# M105.net
KiCad netlist of a schematic drawn in EAGLE
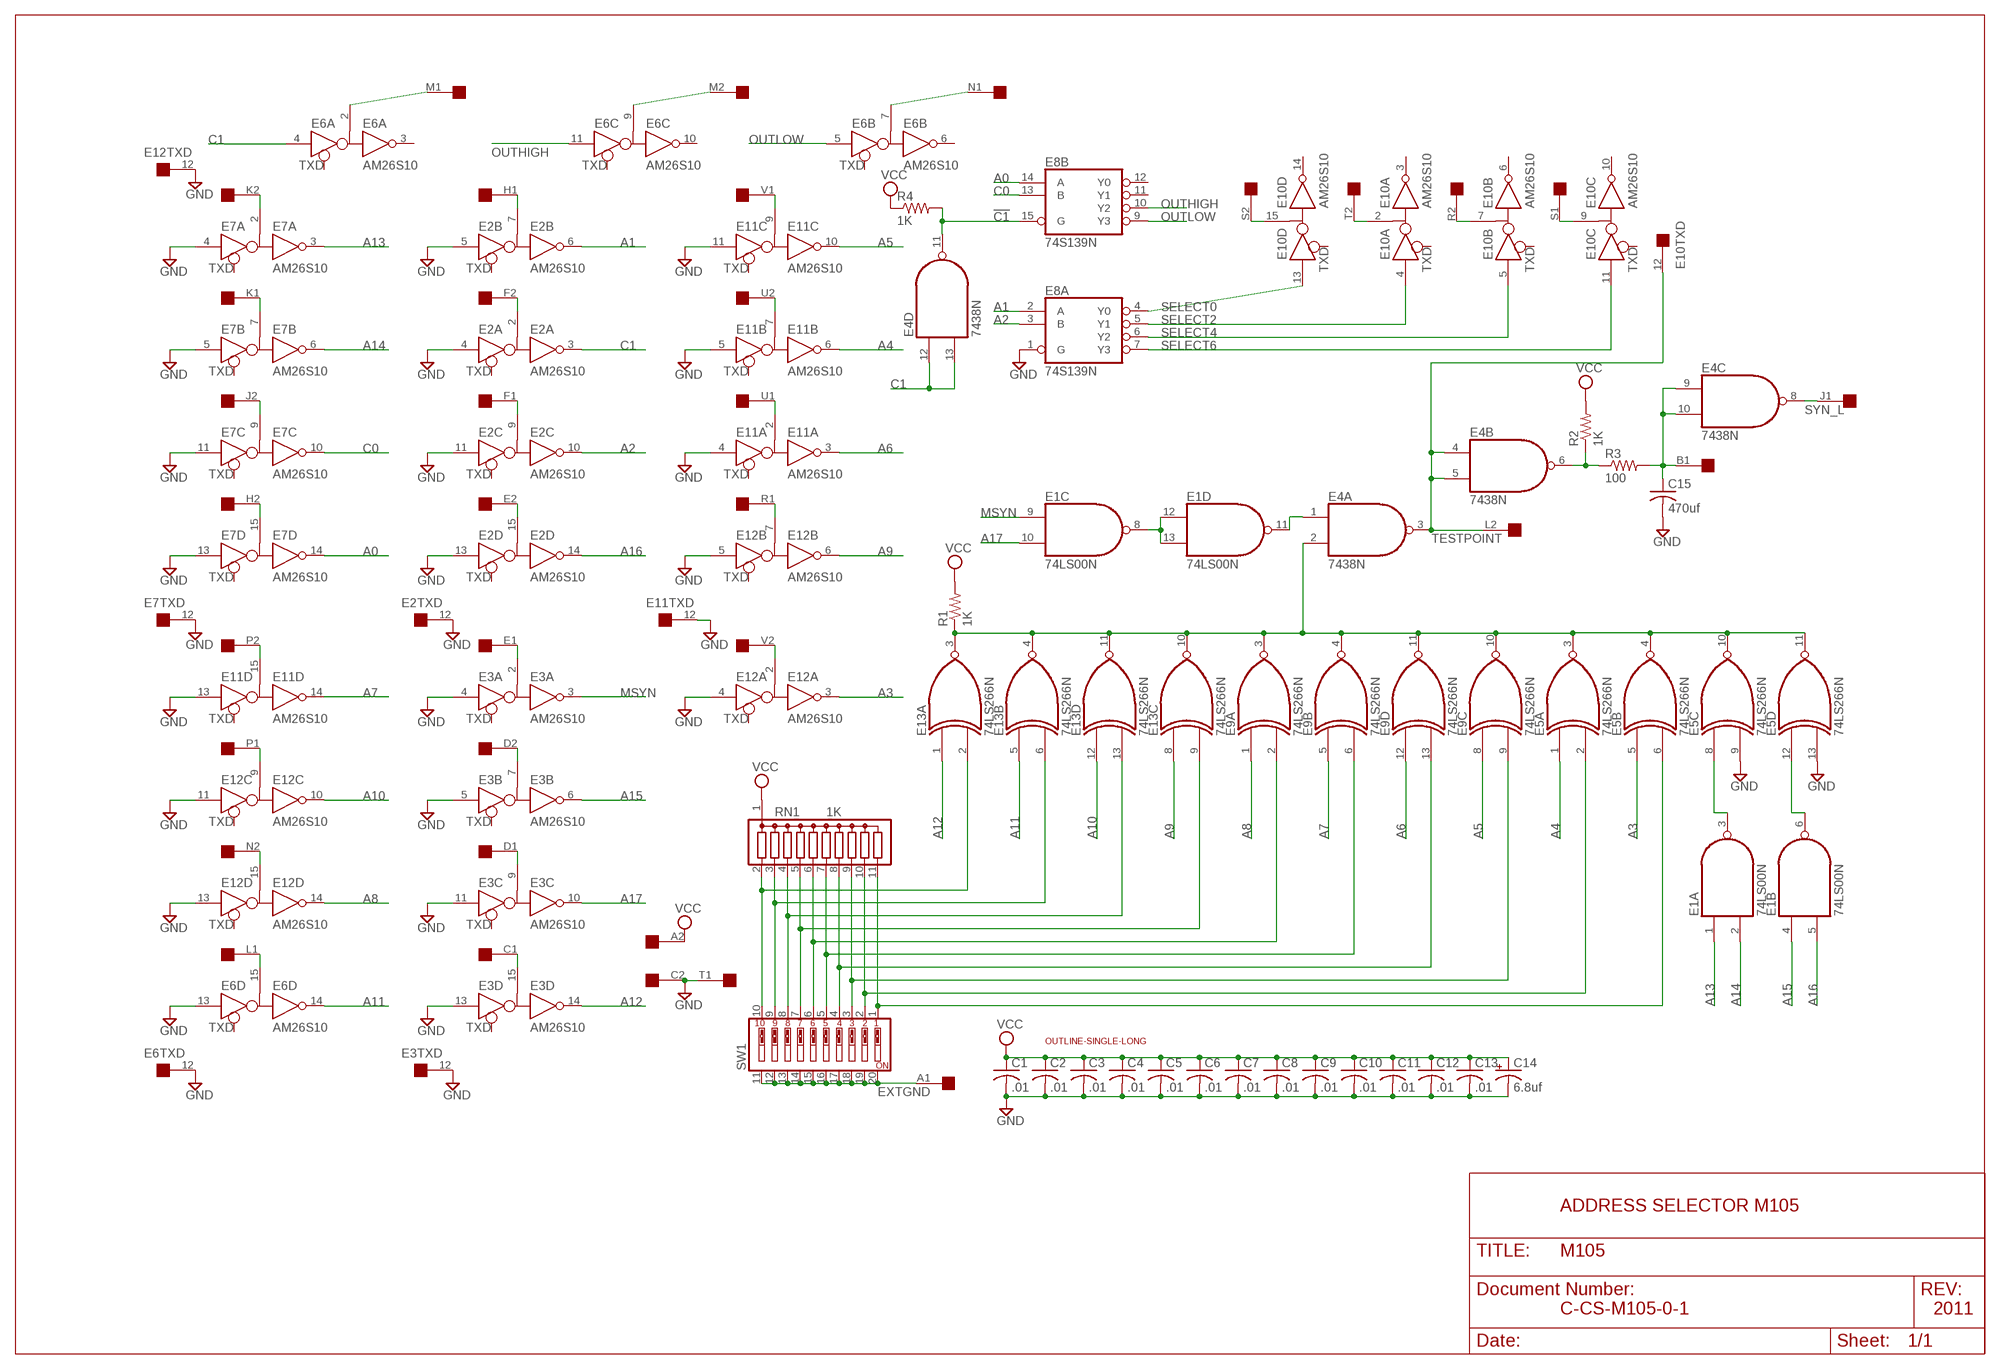
[diagram p0: schematic, sheet 1]

(export (version "E")
  (design (tool "Eeschema 10.0.6"))
  (components
    (comp (ref "C1")
      (value ".01")
      (footprint "eagle-import:C050-025X075")
      (libsource (lib "eagle-import") (part "C-US050-025X075"))
    )
    (comp (ref "C2")
      (value ".01")
      (footprint "eagle-import:C050-025X075")
      (libsource (lib "eagle-import") (part "C-US050-025X075"))
    )
    (comp (ref "C3")
      (value ".01")
      (footprint "eagle-import:C050-025X075")
      (libsource (lib "eagle-import") (part "C-US050-025X075"))
    )
    (comp (ref "C4")
      (value ".01")
      (footprint "eagle-import:C050-025X075")
      (libsource (lib "eagle-import") (part "C-US050-025X075"))
    )
    (comp (ref "C5")
      (value ".01")
      (footprint "eagle-import:C050-025X075")
      (libsource (lib "eagle-import") (part "C-US050-025X075"))
    )
    (comp (ref "C6")
      (value ".01")
      (footprint "eagle-import:C050-025X075")
      (libsource (lib "eagle-import") (part "C-US050-025X075"))
    )
    (comp (ref "C7")
      (value ".01")
      (footprint "eagle-import:C050-025X075")
      (libsource (lib "eagle-import") (part "C-US050-025X075"))
    )
    (comp (ref "C8")
      (value ".01")
      (footprint "eagle-import:C050-025X075")
      (libsource (lib "eagle-import") (part "C-US050-025X075"))
    )
    (comp (ref "C9")
      (value ".01")
      (footprint "eagle-import:C050-025X075")
      (libsource (lib "eagle-import") (part "C-US050-025X075"))
    )
    (comp (ref "C10")
      (value ".01")
      (footprint "eagle-import:C050-025X075")
      (libsource (lib "eagle-import") (part "C-US050-025X075"))
    )
    (comp (ref "C11")
      (value ".01")
      (footprint "eagle-import:C050-025X075")
      (libsource (lib "eagle-import") (part "C-US050-025X075"))
    )
    (comp (ref "C12")
      (value ".01")
      (footprint "eagle-import:C050-025X075")
      (libsource (lib "eagle-import") (part "C-US050-025X075"))
    )
    (comp (ref "C13")
      (value ".01")
      (footprint "eagle-import:C050-025X075")
      (libsource (lib "eagle-import") (part "C-US050-025X075"))
    )
    (comp (ref "C14")
      (value "6.8uf")
      (footprint "eagle-import:E15-5")
      (libsource (lib "eagle-import") (part "CPOL-USE15-5AXIAL"))
    )
    (comp (ref "C15")
      (value "470uf")
      (footprint "eagle-import:C050-025X075")
      (libsource (lib "eagle-import") (part "C-US050-025X075"))
    )
    (comp (ref "E1")
      (value "74LS00N")
      (footprint "eagle-import:DIL14")
      (libsource (lib "eagle-import") (part "7400NLS"))
    )
    (comp (ref "E2")
      (value "AM26S10")
      (footprint "eagle-import:DIL16")
      (libsource (lib "eagle-import") (part "AM26S10"))
    )
    (comp (ref "E3")
      (value "AM26S10")
      (footprint "eagle-import:DIL16")
      (libsource (lib "eagle-import") (part "AM26S10"))
    )
    (comp (ref "E4")
      (value "7438N")
      (footprint "eagle-import:DIL14")
      (libsource (lib "eagle-import") (part "7438N"))
    )
    (comp (ref "E5")
      (value "74LS266N")
      (footprint "eagle-import:DIL14")
      (libsource (lib "eagle-import") (part "74266NLS"))
    )
    (comp (ref "E6")
      (value "AM26S10")
      (footprint "eagle-import:DIL16")
      (libsource (lib "eagle-import") (part "AM26S10"))
    )
    (comp (ref "E7")
      (value "AM26S10")
      (footprint "eagle-import:DIL16")
      (libsource (lib "eagle-import") (part "AM26S10"))
    )
    (comp (ref "E8")
      (value "74S139N")
      (footprint "eagle-import:DIL16")
      (libsource (lib "eagle-import") (part "74139NS"))
    )
    (comp (ref "E9")
      (value "74LS266N")
      (footprint "eagle-import:DIL14")
      (libsource (lib "eagle-import") (part "74266NLS"))
    )
    (comp (ref "E10")
      (value "AM26S10")
      (footprint "eagle-import:DIL16")
      (libsource (lib "eagle-import") (part "AM26S10"))
    )
    (comp (ref "E11")
      (value "AM26S10")
      (footprint "eagle-import:DIL16")
      (libsource (lib "eagle-import") (part "AM26S10"))
    )
    (comp (ref "E12")
      (value "AM26S10")
      (footprint "eagle-import:DIL16")
      (libsource (lib "eagle-import") (part "AM26S10"))
    )
    (comp (ref "E13")
      (value "74LS266N")
      (footprint "eagle-import:DIL14")
      (libsource (lib "eagle-import") (part "74266NLS"))
    )
    (comp (ref "R1")
      (value "1K")
      (footprint "eagle-import:0207_10")
      (libsource (lib "eagle-import") (part "R-US_0207/10"))
    )
    (comp (ref "R2")
      (value "1K")
      (footprint "eagle-import:0207_10")
      (libsource (lib "eagle-import") (part "R-US_0207/10"))
    )
    (comp (ref "R3")
      (value "100")
      (footprint "eagle-import:0207_10")
      (libsource (lib "eagle-import") (part "R-US_0207/10"))
    )
    (comp (ref "R4")
      (value "1K")
      (footprint "eagle-import:0207_10")
      (libsource (lib "eagle-import") (part "R-US_0207/10"))
    )
    (comp (ref "RN1")
      (value "1K")
      (footprint "eagle-import:SIL11")
      (libsource (lib "eagle-import") (part "G10R"))
    )
    (comp (ref "SW1")
      (value "SW_DIP-10")
      (footprint "eagle-import:EDG-10")
      (libsource (lib "eagle-import") (part "SW_DIP-10"))
    )
    (comp (ref "U$1")
      (value "SINGLE")
      (footprint "eagle-import:EDGE-CON2")
      (libsource (lib "eagle-import") (part "SINGLE"))
    )
    (comp (ref "U$2")
      (value "OUTLINE-SINGLE-LONG")
      (footprint "eagle-import:SINGLE-LONG")
      (libsource (lib "eagle-import") (part "OUTLINE-SINGLE-LONG"))
    )
  )
  (nets
    (net (code "1") (name "/A0") (class "Default")
      (node (ref "E7") (pin "14") (pinfunction "R_14") (pintype "output"))
      (node (ref "E8") (pin "14") (pinfunction "A_14") (pintype "input"))
    )
    (net (code "2") (name "/A1") (class "Default")
      (node (ref "E2") (pin "6") (pinfunction "R_6") (pintype "output"))
      (node (ref "E8") (pin "2") (pinfunction "A_2") (pintype "input"))
    )
    (net (code "3") (name "/A2") (class "Default")
      (node (ref "E2") (pin "10") (pinfunction "R_10") (pintype "output"))
      (node (ref "E8") (pin "3") (pinfunction "B_3") (pintype "input"))
    )
    (net (code "4") (name "/A3") (class "Default")
      (node (ref "E12") (pin "3") (pinfunction "R_3") (pintype "output"))
      (node (ref "E5") (pin "5") (pinfunction "I0_5") (pintype "input"))
    )
    (net (code "5") (name "/A4") (class "Default")
      (node (ref "E11") (pin "6") (pinfunction "R_6") (pintype "output"))
      (node (ref "E5") (pin "1") (pinfunction "I0_1") (pintype "input"))
    )
    (net (code "6") (name "/A5") (class "Default")
      (node (ref "E11") (pin "10") (pinfunction "R_10") (pintype "output"))
      (node (ref "E9") (pin "8") (pinfunction "I0_8") (pintype "input"))
    )
    (net (code "7") (name "/A6") (class "Default")
      (node (ref "E11") (pin "3") (pinfunction "R_3") (pintype "output"))
      (node (ref "E9") (pin "12") (pinfunction "I0_12") (pintype "input"))
    )
    (net (code "8") (name "/A7") (class "Default")
      (node (ref "E11") (pin "14") (pinfunction "R_14") (pintype "output"))
      (node (ref "E9") (pin "5") (pinfunction "I0_5") (pintype "input"))
    )
    (net (code "9") (name "/A8") (class "Default")
      (node (ref "E12") (pin "14") (pinfunction "R_14") (pintype "output"))
      (node (ref "E9") (pin "1") (pinfunction "I0_1") (pintype "input"))
    )
    (net (code "10") (name "/A9") (class "Default")
      (node (ref "E12") (pin "6") (pinfunction "R_6") (pintype "output"))
      (node (ref "E13") (pin "8") (pinfunction "I0_8") (pintype "input"))
    )
    (net (code "11") (name "/A10") (class "Default")
      (node (ref "E12") (pin "10") (pinfunction "R_10") (pintype "output"))
      (node (ref "E13") (pin "12") (pinfunction "I0_12") (pintype "input"))
    )
    (net (code "12") (name "/A11") (class "Default")
      (node (ref "E13") (pin "5") (pinfunction "I0_5") (pintype "input"))
      (node (ref "E6") (pin "14") (pinfunction "R_14") (pintype "output"))
    )
    (net (code "13") (name "/A12") (class "Default")
      (node (ref "E13") (pin "1") (pinfunction "I0_1") (pintype "input"))
      (node (ref "E3") (pin "14") (pinfunction "R_14") (pintype "output"))
    )
    (net (code "14") (name "/A13") (class "Default")
      (node (ref "E1") (pin "1") (pinfunction "I0_1") (pintype "input"))
      (node (ref "E7") (pin "3") (pinfunction "R_3") (pintype "output"))
    )
    (net (code "15") (name "/A14") (class "Default")
      (node (ref "E1") (pin "2") (pinfunction "I1_2") (pintype "input"))
      (node (ref "E7") (pin "6") (pinfunction "R_6") (pintype "output"))
    )
    (net (code "16") (name "/A15") (class "Default")
      (node (ref "E1") (pin "4") (pinfunction "I0_4") (pintype "input"))
      (node (ref "E3") (pin "6") (pinfunction "R_6") (pintype "output"))
    )
    (net (code "17") (name "/A16") (class "Default")
      (node (ref "E1") (pin "5") (pinfunction "I1_5") (pintype "input"))
      (node (ref "E2") (pin "14") (pinfunction "R_14") (pintype "output"))
    )
    (net (code "18") (name "/A17") (class "Default")
      (node (ref "E1") (pin "10") (pinfunction "I1_10") (pintype "input"))
      (node (ref "E3") (pin "10") (pinfunction "R_10") (pintype "output"))
    )
    (net (code "19") (name "/C0") (class "Default")
      (node (ref "E7") (pin "10") (pinfunction "R_10") (pintype "output"))
      (node (ref "E8") (pin "13") (pinfunction "B_13") (pintype "input"))
    )
    (net (code "20") (name "/C1") (class "Default")
      (node (ref "E2") (pin "3") (pinfunction "R_3") (pintype "output"))
      (node (ref "E4") (pin "12") (pinfunction "I0_12") (pintype "input"))
      (node (ref "E4") (pin "13") (pinfunction "I1_13") (pintype "input"))
      (node (ref "E6") (pin "4") (pinfunction "D_4") (pintype "input"))
    )
    (net (code "21") (name "/EXTGND") (class "Default")
      (node (ref "SW1") (pin "11") (pinfunction "11_11") (pintype "passive"))
      (node (ref "SW1") (pin "12") (pinfunction "12_12") (pintype "passive"))
      (node (ref "SW1") (pin "13") (pinfunction "13_13") (pintype "passive"))
      (node (ref "SW1") (pin "14") (pinfunction "14_14") (pintype "passive"))
      (node (ref "SW1") (pin "15") (pinfunction "15_15") (pintype "passive"))
      (node (ref "SW1") (pin "16") (pinfunction "16_16") (pintype "passive"))
      (node (ref "SW1") (pin "17") (pinfunction "17_17") (pintype "passive"))
      (node (ref "SW1") (pin "18") (pinfunction "18_18") (pintype "passive"))
      (node (ref "SW1") (pin "19") (pinfunction "19_19") (pintype "passive"))
      (node (ref "SW1") (pin "20") (pinfunction "20_20") (pintype "passive"))
      (node (ref "U$1") (pin "A1") (pinfunction "1_A1") (pintype "bidirectional"))
    )
    (net (code "22") (name "/MSYN") (class "Default")
      (node (ref "E1") (pin "9") (pinfunction "I0_9") (pintype "input"))
      (node (ref "E3") (pin "3") (pinfunction "R_3") (pintype "output"))
    )
    (net (code "23") (name "/OUTHIGH") (class "Default")
      (node (ref "E6") (pin "11") (pinfunction "D_11") (pintype "input"))
      (node (ref "E8") (pin "10") (pinfunction "Y2_10") (pintype "output"))
    )
    (net (code "24") (name "/OUTLOW") (class "Default")
      (node (ref "E6") (pin "5") (pinfunction "D_5") (pintype "input"))
      (node (ref "E8") (pin "9") (pinfunction "Y3_9") (pintype "output"))
    )
    (net (code "25") (name "/SELECT0") (class "Default")
      (node (ref "E10") (pin "13") (pinfunction "D_13") (pintype "input"))
      (node (ref "E8") (pin "4") (pinfunction "Y0_4") (pintype "output"))
    )
    (net (code "26") (name "/SELECT2") (class "Default")
      (node (ref "E10") (pin "4") (pinfunction "D_4") (pintype "input"))
      (node (ref "E8") (pin "5") (pinfunction "Y1_5") (pintype "output"))
    )
    (net (code "27") (name "/SELECT4") (class "Default")
      (node (ref "E10") (pin "5") (pinfunction "D_5") (pintype "input"))
      (node (ref "E8") (pin "6") (pinfunction "Y2_6") (pintype "output"))
    )
    (net (code "28") (name "/SELECT6") (class "Default")
      (node (ref "E10") (pin "11") (pinfunction "D_11") (pintype "input"))
      (node (ref "E8") (pin "7") (pinfunction "Y3_7") (pintype "output"))
    )
    (net (code "29") (name "/SYN_L") (class "Default")
      (node (ref "E4") (pin "8") (pinfunction "O_8") (pintype "open_collector"))
      (node (ref "U$1") (pin "J1") (pinfunction "1_J1") (pintype "bidirectional"))
    )
    (net (code "30") (name "/TESTPOINT") (class "Default")
      (node (ref "E10") (pin "12") (pinfunction "TXD_12") (pintype "input"))
      (node (ref "E4") (pin "3") (pinfunction "O_3") (pintype "open_collector"))
      (node (ref "E4") (pin "4") (pinfunction "I0_4") (pintype "input"))
      (node (ref "E4") (pin "5") (pinfunction "I1_5") (pintype "input"))
      (node (ref "U$1") (pin "L2") (pinfunction "1_L2") (pintype "bidirectional"))
    )
    (net (code "31") (name "/~{C1}") (class "Default")
      (node (ref "E4") (pin "11") (pinfunction "O_11") (pintype "open_collector"))
      (node (ref "E8") (pin "15") (pinfunction "G_15") (pintype "input"))
      (node (ref "R4") (pin "2") (pinfunction "2_2") (pintype "passive"))
    )
    (net (code "32") (name "GND") (class "Default")
      (node (ref "C1") (pin "2") (pinfunction "2_2") (pintype "passive"))
      (node (ref "C10") (pin "2") (pinfunction "2_2") (pintype "passive"))
      (node (ref "C11") (pin "2") (pinfunction "2_2") (pintype "passive"))
      (node (ref "C12") (pin "2") (pinfunction "2_2") (pintype "passive"))
      (node (ref "C13") (pin "2") (pinfunction "2_2") (pintype "passive"))
      (node (ref "C14") (pin "-") (pinfunction "-_-") (pintype "passive"))
      (node (ref "C15") (pin "2") (pinfunction "2_2") (pintype "passive"))
      (node (ref "C2") (pin "2") (pinfunction "2_2") (pintype "passive"))
      (node (ref "C3") (pin "2") (pinfunction "2_2") (pintype "passive"))
      (node (ref "C4") (pin "2") (pinfunction "2_2") (pintype "passive"))
      (node (ref "C5") (pin "2") (pinfunction "2_2") (pintype "passive"))
      (node (ref "C6") (pin "2") (pinfunction "2_2") (pintype "passive"))
      (node (ref "C7") (pin "2") (pinfunction "2_2") (pintype "passive"))
      (node (ref "C8") (pin "2") (pinfunction "2_2") (pintype "passive"))
      (node (ref "C9") (pin "2") (pinfunction "2_2") (pintype "passive"))
      (node (ref "E11") (pin "11") (pinfunction "D_11") (pintype "input"))
      (node (ref "E11") (pin "12") (pinfunction "TXD_12") (pintype "input"))
      (node (ref "E11") (pin "13") (pinfunction "D_13") (pintype "input"))
      (node (ref "E11") (pin "4") (pinfunction "D_4") (pintype "input"))
      (node (ref "E11") (pin "5") (pinfunction "D_5") (pintype "input"))
      (node (ref "E12") (pin "11") (pinfunction "D_11") (pintype "input"))
      (node (ref "E12") (pin "12") (pinfunction "TXD_12") (pintype "input"))
      (node (ref "E12") (pin "13") (pinfunction "D_13") (pintype "input"))
      (node (ref "E12") (pin "4") (pinfunction "D_4") (pintype "input"))
      (node (ref "E12") (pin "5") (pinfunction "D_5") (pintype "input"))
      (node (ref "E2") (pin "11") (pinfunction "D_11") (pintype "input"))
      (node (ref "E2") (pin "12") (pinfunction "TXD_12") (pintype "input"))
      (node (ref "E2") (pin "13") (pinfunction "D_13") (pintype "input"))
      (node (ref "E2") (pin "4") (pinfunction "D_4") (pintype "input"))
      (node (ref "E2") (pin "5") (pinfunction "D_5") (pintype "input"))
      (node (ref "E3") (pin "11") (pinfunction "D_11") (pintype "input"))
      (node (ref "E3") (pin "12") (pinfunction "TXD_12") (pintype "input"))
      (node (ref "E3") (pin "13") (pinfunction "D_13") (pintype "input"))
      (node (ref "E3") (pin "4") (pinfunction "D_4") (pintype "input"))
      (node (ref "E3") (pin "5") (pinfunction "D_5") (pintype "input"))
      (node (ref "E5") (pin "13") (pinfunction "I1_13") (pintype "input"))
      (node (ref "E5") (pin "9") (pinfunction "I1_9") (pintype "input"))
      (node (ref "E6") (pin "12") (pinfunction "TXD_12") (pintype "input"))
      (node (ref "E6") (pin "13") (pinfunction "D_13") (pintype "input"))
      (node (ref "E7") (pin "11") (pinfunction "D_11") (pintype "input"))
      (node (ref "E7") (pin "12") (pinfunction "TXD_12") (pintype "input"))
      (node (ref "E7") (pin "13") (pinfunction "D_13") (pintype "input"))
      (node (ref "E7") (pin "4") (pinfunction "D_4") (pintype "input"))
      (node (ref "E7") (pin "5") (pinfunction "D_5") (pintype "input"))
      (node (ref "E8") (pin "1") (pinfunction "G_1") (pintype "input"))
      (node (ref "U$1") (pin "C2") (pinfunction "1_C2") (pintype "bidirectional"))
      (node (ref "U$1") (pin "T1") (pinfunction "1_T1") (pintype "bidirectional"))
    )
    (net (code "33") (name "Net-(E1A-O)") (class "Default")
      (node (ref "E1") (pin "3") (pinfunction "O_3") (pintype "output"))
      (node (ref "E5") (pin "8") (pinfunction "I0_8") (pintype "input"))
    )
    (net (code "34") (name "Net-(E1B-O)") (class "Default")
      (node (ref "E1") (pin "6") (pinfunction "O_6") (pintype "output"))
      (node (ref "E5") (pin "12") (pinfunction "I0_12") (pintype "input"))
    )
    (net (code "35") (name "Net-(E1C-O)") (class "Default")
      (node (ref "E1") (pin "12") (pinfunction "I0_12") (pintype "input"))
      (node (ref "E1") (pin "13") (pinfunction "I1_13") (pintype "input"))
      (node (ref "E1") (pin "8") (pinfunction "O_8") (pintype "output"))
    )
    (net (code "36") (name "Net-(E1D-O)") (class "Default")
      (node (ref "E1") (pin "11") (pinfunction "O_11") (pintype "output"))
      (node (ref "E4") (pin "1") (pinfunction "I0_1") (pintype "input"))
    )
    (net (code "37") (name "Net-(E2A-B)") (class "Default")
      (node (ref "E2") (pin "2") (pinfunction "B_2") (pintype "bidirectional"))
      (node (ref "U$1") (pin "F2") (pinfunction "1_F2") (pintype "bidirectional"))
    )
    (net (code "38") (name "Net-(E2B-B)") (class "Default")
      (node (ref "E2") (pin "7") (pinfunction "B_7") (pintype "bidirectional"))
      (node (ref "U$1") (pin "H1") (pinfunction "1_H1") (pintype "bidirectional"))
    )
    (net (code "39") (name "Net-(E2C-B)") (class "Default")
      (node (ref "E2") (pin "9") (pinfunction "B_9") (pintype "bidirectional"))
      (node (ref "U$1") (pin "F1") (pinfunction "1_F1") (pintype "bidirectional"))
    )
    (net (code "40") (name "Net-(E2D-B)") (class "Default")
      (node (ref "E2") (pin "15") (pinfunction "B_15") (pintype "bidirectional"))
      (node (ref "U$1") (pin "E2") (pinfunction "1_E2") (pintype "bidirectional"))
    )
    (net (code "41") (name "Net-(E3A-B)") (class "Default")
      (node (ref "E3") (pin "2") (pinfunction "B_2") (pintype "bidirectional"))
      (node (ref "U$1") (pin "E1") (pinfunction "1_E1") (pintype "bidirectional"))
    )
    (net (code "42") (name "Net-(E3B-B)") (class "Default")
      (node (ref "E3") (pin "7") (pinfunction "B_7") (pintype "bidirectional"))
      (node (ref "U$1") (pin "D2") (pinfunction "1_D2") (pintype "bidirectional"))
    )
    (net (code "43") (name "Net-(E3C-B)") (class "Default")
      (node (ref "E3") (pin "9") (pinfunction "B_9") (pintype "bidirectional"))
      (node (ref "U$1") (pin "D1") (pinfunction "1_D1") (pintype "bidirectional"))
    )
    (net (code "44") (name "Net-(E3D-B)") (class "Default")
      (node (ref "E3") (pin "15") (pinfunction "B_15") (pintype "bidirectional"))
      (node (ref "U$1") (pin "C1") (pinfunction "1_C1") (pintype "bidirectional"))
    )
    (net (code "45") (name "Net-(E4B-O)") (class "Default")
      (node (ref "E4") (pin "6") (pinfunction "O_6") (pintype "open_collector"))
      (node (ref "R2") (pin "1") (pinfunction "1_1") (pintype "passive"))
      (node (ref "R3") (pin "1") (pinfunction "1_1") (pintype "passive"))
    )
    (net (code "46") (name "Net-(E4C-I0)") (class "Default")
      (node (ref "C15") (pin "1") (pinfunction "1_1") (pintype "passive"))
      (node (ref "E4") (pin "10") (pinfunction "I1_10") (pintype "input"))
      (node (ref "E4") (pin "9") (pinfunction "I0_9") (pintype "input"))
      (node (ref "R3") (pin "2") (pinfunction "2_2") (pintype "passive"))
      (node (ref "U$1") (pin "B1") (pinfunction "1_B1") (pintype "bidirectional"))
    )
    (net (code "47") (name "Net-(E5A-I1)") (class "Default")
      (node (ref "E5") (pin "2") (pinfunction "I1_2") (pintype "input"))
      (node (ref "RN1") (pin "10") (pinfunction "10_10") (pintype "passive"))
      (node (ref "SW1") (pin "2") (pinfunction "2_2") (pintype "passive"))
    )
    (net (code "48") (name "Net-(E5B-I1)") (class "Default")
      (node (ref "E5") (pin "6") (pinfunction "I1_6") (pintype "input"))
      (node (ref "RN1") (pin "11") (pinfunction "11_11") (pintype "passive"))
      (node (ref "SW1") (pin "1") (pinfunction "1_1") (pintype "passive"))
    )
    (net (code "49") (name "Net-(E6A-B)") (class "Default")
      (node (ref "E6") (pin "2") (pinfunction "B_2") (pintype "bidirectional"))
      (node (ref "U$1") (pin "M1") (pinfunction "1_M1") (pintype "bidirectional"))
    )
    (net (code "50") (name "Net-(E6B-B)") (class "Default")
      (node (ref "E6") (pin "7") (pinfunction "B_7") (pintype "bidirectional"))
      (node (ref "U$1") (pin "N1") (pinfunction "1_N1") (pintype "bidirectional"))
    )
    (net (code "51") (name "Net-(E6C-B)") (class "Default")
      (node (ref "E6") (pin "9") (pinfunction "B_9") (pintype "bidirectional"))
      (node (ref "U$1") (pin "M2") (pinfunction "1_M2") (pintype "bidirectional"))
    )
    (net (code "52") (name "Net-(E6D-B)") (class "Default")
      (node (ref "E6") (pin "15") (pinfunction "B_15") (pintype "bidirectional"))
      (node (ref "U$1") (pin "L1") (pinfunction "1_L1") (pintype "bidirectional"))
    )
    (net (code "53") (name "Net-(E7A-B)") (class "Default")
      (node (ref "E7") (pin "2") (pinfunction "B_2") (pintype "bidirectional"))
      (node (ref "U$1") (pin "K2") (pinfunction "1_K2") (pintype "bidirectional"))
    )
    (net (code "54") (name "Net-(E7B-B)") (class "Default")
      (node (ref "E7") (pin "7") (pinfunction "B_7") (pintype "bidirectional"))
      (node (ref "U$1") (pin "K1") (pinfunction "1_K1") (pintype "bidirectional"))
    )
    (net (code "55") (name "Net-(E7C-B)") (class "Default")
      (node (ref "E7") (pin "9") (pinfunction "B_9") (pintype "bidirectional"))
      (node (ref "U$1") (pin "J2") (pinfunction "1_J2") (pintype "bidirectional"))
    )
    (net (code "56") (name "Net-(E7D-B)") (class "Default")
      (node (ref "E7") (pin "15") (pinfunction "B_15") (pintype "bidirectional"))
      (node (ref "U$1") (pin "H2") (pinfunction "1_H2") (pintype "bidirectional"))
    )
    (net (code "57") (name "Net-(E9A-I1)") (class "Default")
      (node (ref "E9") (pin "2") (pinfunction "I1_2") (pintype "input"))
      (node (ref "RN1") (pin "6") (pinfunction "6_6") (pintype "passive"))
      (node (ref "SW1") (pin "6") (pinfunction "6_6") (pintype "passive"))
    )
    (net (code "58") (name "Net-(E9B-I1)") (class "Default")
      (node (ref "E9") (pin "6") (pinfunction "I1_6") (pintype "input"))
      (node (ref "RN1") (pin "7") (pinfunction "7_7") (pintype "passive"))
      (node (ref "SW1") (pin "5") (pinfunction "5_5") (pintype "passive"))
    )
    (net (code "59") (name "Net-(E9C-I1)") (class "Default")
      (node (ref "E9") (pin "9") (pinfunction "I1_9") (pintype "input"))
      (node (ref "RN1") (pin "9") (pinfunction "9_9") (pintype "passive"))
      (node (ref "SW1") (pin "3") (pinfunction "3_3") (pintype "passive"))
    )
    (net (code "60") (name "Net-(E9D-I1)") (class "Default")
      (node (ref "E9") (pin "13") (pinfunction "I1_13") (pintype "input"))
      (node (ref "RN1") (pin "8") (pinfunction "8_8") (pintype "passive"))
      (node (ref "SW1") (pin "4") (pinfunction "4_4") (pintype "passive"))
    )
    (net (code "61") (name "Net-(E10A-B)") (class "Default")
      (node (ref "E10") (pin "2") (pinfunction "B_2") (pintype "bidirectional"))
      (node (ref "U$1") (pin "T2") (pinfunction "1_T2") (pintype "bidirectional"))
    )
    (net (code "62") (name "Net-(E10B-B)") (class "Default")
      (node (ref "E10") (pin "7") (pinfunction "B_7") (pintype "bidirectional"))
      (node (ref "U$1") (pin "R2") (pinfunction "1_R2") (pintype "bidirectional"))
    )
    (net (code "63") (name "Net-(E10C-B)") (class "Default")
      (node (ref "E10") (pin "9") (pinfunction "B_9") (pintype "bidirectional"))
      (node (ref "U$1") (pin "S1") (pinfunction "1_S1") (pintype "bidirectional"))
    )
    (net (code "64") (name "Net-(E10D-B)") (class "Default")
      (node (ref "E10") (pin "15") (pinfunction "B_15") (pintype "bidirectional"))
      (node (ref "U$1") (pin "S2") (pinfunction "1_S2") (pintype "bidirectional"))
    )
    (net (code "65") (name "Net-(E11A-B)") (class "Default")
      (node (ref "E11") (pin "2") (pinfunction "B_2") (pintype "bidirectional"))
      (node (ref "U$1") (pin "U1") (pinfunction "1_U1") (pintype "bidirectional"))
    )
    (net (code "66") (name "Net-(E11B-B)") (class "Default")
      (node (ref "E11") (pin "7") (pinfunction "B_7") (pintype "bidirectional"))
      (node (ref "U$1") (pin "U2") (pinfunction "1_U2") (pintype "bidirectional"))
    )
    (net (code "67") (name "Net-(E11C-B)") (class "Default")
      (node (ref "E11") (pin "9") (pinfunction "B_9") (pintype "bidirectional"))
      (node (ref "U$1") (pin "V1") (pinfunction "1_V1") (pintype "bidirectional"))
    )
    (net (code "68") (name "Net-(E11D-B)") (class "Default")
      (node (ref "E11") (pin "15") (pinfunction "B_15") (pintype "bidirectional"))
      (node (ref "U$1") (pin "P2") (pinfunction "1_P2") (pintype "bidirectional"))
    )
    (net (code "69") (name "Net-(E12A-B)") (class "Default")
      (node (ref "E12") (pin "2") (pinfunction "B_2") (pintype "bidirectional"))
      (node (ref "U$1") (pin "V2") (pinfunction "1_V2") (pintype "bidirectional"))
    )
    (net (code "70") (name "Net-(E12B-B)") (class "Default")
      (node (ref "E12") (pin "7") (pinfunction "B_7") (pintype "bidirectional"))
      (node (ref "U$1") (pin "R1") (pinfunction "1_R1") (pintype "bidirectional"))
    )
    (net (code "71") (name "Net-(E12C-B)") (class "Default")
      (node (ref "E12") (pin "9") (pinfunction "B_9") (pintype "bidirectional"))
      (node (ref "U$1") (pin "P1") (pinfunction "1_P1") (pintype "bidirectional"))
    )
    (net (code "72") (name "Net-(E12D-B)") (class "Default")
      (node (ref "E12") (pin "15") (pinfunction "B_15") (pintype "bidirectional"))
      (node (ref "U$1") (pin "N2") (pinfunction "1_N2") (pintype "bidirectional"))
    )
    (net (code "73") (name "Net-(E13A-I1)") (class "Default")
      (node (ref "E13") (pin "2") (pinfunction "I1_2") (pintype "input"))
      (node (ref "RN1") (pin "2") (pinfunction "2_2") (pintype "passive"))
      (node (ref "SW1") (pin "10") (pinfunction "10_10") (pintype "passive"))
    )
    (net (code "74") (name "Net-(E13A-O)") (class "Default")
      (node (ref "E13") (pin "10") (pinfunction "O_10") (pintype "open_collector"))
      (node (ref "E13") (pin "11") (pinfunction "O_11") (pintype "open_collector"))
      (node (ref "E13") (pin "3") (pinfunction "O_3") (pintype "open_collector"))
      (node (ref "E13") (pin "4") (pinfunction "O_4") (pintype "open_collector"))
      (node (ref "E4") (pin "2") (pinfunction "I1_2") (pintype "input"))
      (node (ref "E5") (pin "10") (pinfunction "O_10") (pintype "open_collector"))
      (node (ref "E5") (pin "11") (pinfunction "O_11") (pintype "open_collector"))
      (node (ref "E5") (pin "3") (pinfunction "O_3") (pintype "open_collector"))
      (node (ref "E5") (pin "4") (pinfunction "O_4") (pintype "open_collector"))
      (node (ref "E9") (pin "10") (pinfunction "O_10") (pintype "open_collector"))
      (node (ref "E9") (pin "11") (pinfunction "O_11") (pintype "open_collector"))
      (node (ref "E9") (pin "3") (pinfunction "O_3") (pintype "open_collector"))
      (node (ref "E9") (pin "4") (pinfunction "O_4") (pintype "open_collector"))
      (node (ref "R1") (pin "1") (pinfunction "1_1") (pintype "passive"))
    )
    (net (code "75") (name "Net-(E13B-I1)") (class "Default")
      (node (ref "E13") (pin "6") (pinfunction "I1_6") (pintype "input"))
      (node (ref "RN1") (pin "3") (pinfunction "3_3") (pintype "passive"))
      (node (ref "SW1") (pin "9") (pinfunction "9_9") (pintype "passive"))
    )
    (net (code "76") (name "Net-(E13C-I1)") (class "Default")
      (node (ref "E13") (pin "9") (pinfunction "I1_9") (pintype "input"))
      (node (ref "RN1") (pin "5") (pinfunction "5_5") (pintype "passive"))
      (node (ref "SW1") (pin "7") (pinfunction "7_7") (pintype "passive"))
    )
    (net (code "77") (name "Net-(E13D-I1)") (class "Default")
      (node (ref "E13") (pin "13") (pinfunction "I1_13") (pintype "input"))
      (node (ref "RN1") (pin "4") (pinfunction "4_4") (pintype "passive"))
      (node (ref "SW1") (pin "8") (pinfunction "8_8") (pintype "passive"))
    )
    (net (code "78") (name "VCC") (class "Default")
      (node (ref "C1") (pin "1") (pinfunction "1_1") (pintype "passive"))
      (node (ref "C10") (pin "1") (pinfunction "1_1") (pintype "passive"))
      (node (ref "C11") (pin "1") (pinfunction "1_1") (pintype "passive"))
      (node (ref "C12") (pin "1") (pinfunction "1_1") (pintype "passive"))
      (node (ref "C13") (pin "1") (pinfunction "1_1") (pintype "passive"))
      (node (ref "C14") (pin "+") (pinfunction "+_+") (pintype "passive"))
      (node (ref "C2") (pin "1") (pinfunction "1_1") (pintype "passive"))
      (node (ref "C3") (pin "1") (pinfunction "1_1") (pintype "passive"))
      (node (ref "C4") (pin "1") (pinfunction "1_1") (pintype "passive"))
      (node (ref "C5") (pin "1") (pinfunction "1_1") (pintype "passive"))
      (node (ref "C6") (pin "1") (pinfunction "1_1") (pintype "passive"))
      (node (ref "C7") (pin "1") (pinfunction "1_1") (pintype "passive"))
      (node (ref "C8") (pin "1") (pinfunction "1_1") (pintype "passive"))
      (node (ref "C9") (pin "1") (pinfunction "1_1") (pintype "passive"))
      (node (ref "R1") (pin "2") (pinfunction "2_2") (pintype "passive"))
      (node (ref "R2") (pin "2") (pinfunction "2_2") (pintype "passive"))
      (node (ref "R4") (pin "1") (pinfunction "1_1") (pintype "passive"))
      (node (ref "RN1") (pin "1") (pinfunction "1_1") (pintype "passive"))
      (node (ref "U$1") (pin "A2") (pinfunction "1_A2") (pintype "bidirectional"))
    )
    (net (code "79") (name "unconnected-(E6A-R-Pad3)") (class "Default")
      (node (ref "E6") (pin "3") (pinfunction "R_3") (pintype "output"))
    )
    (net (code "80") (name "unconnected-(E6B-R-Pad6)") (class "Default")
      (node (ref "E6") (pin "6") (pinfunction "R_6") (pintype "output"))
    )
    (net (code "81") (name "unconnected-(E6C-R-Pad10)") (class "Default")
      (node (ref "E6") (pin "10") (pinfunction "R_10") (pintype "output"))
    )
    (net (code "82") (name "unconnected-(E8B-Y0-Pad12)") (class "Default")
      (node (ref "E8") (pin "12") (pinfunction "Y0_12") (pintype "output"))
    )
    (net (code "83") (name "unconnected-(E8B-Y1-Pad11)") (class "Default")
      (node (ref "E8") (pin "11") (pinfunction "Y1_11") (pintype "output"))
    )
    (net (code "84") (name "unconnected-(E10A-R-Pad3)") (class "Default")
      (node (ref "E10") (pin "3") (pinfunction "R_3") (pintype "output"))
    )
    (net (code "85") (name "unconnected-(E10B-R-Pad6)") (class "Default")
      (node (ref "E10") (pin "6") (pinfunction "R_6") (pintype "output"))
    )
    (net (code "86") (name "unconnected-(E10C-R-Pad10)") (class "Default")
      (node (ref "E10") (pin "10") (pinfunction "R_10") (pintype "output"))
    )
    (net (code "87") (name "unconnected-(E10D-R-Pad14)") (class "Default")
      (node (ref "E10") (pin "14") (pinfunction "R_14") (pintype "output"))
    )
  )
)
